# SCH.net
KiCad netlist of a schematic drawn in EasyEDA
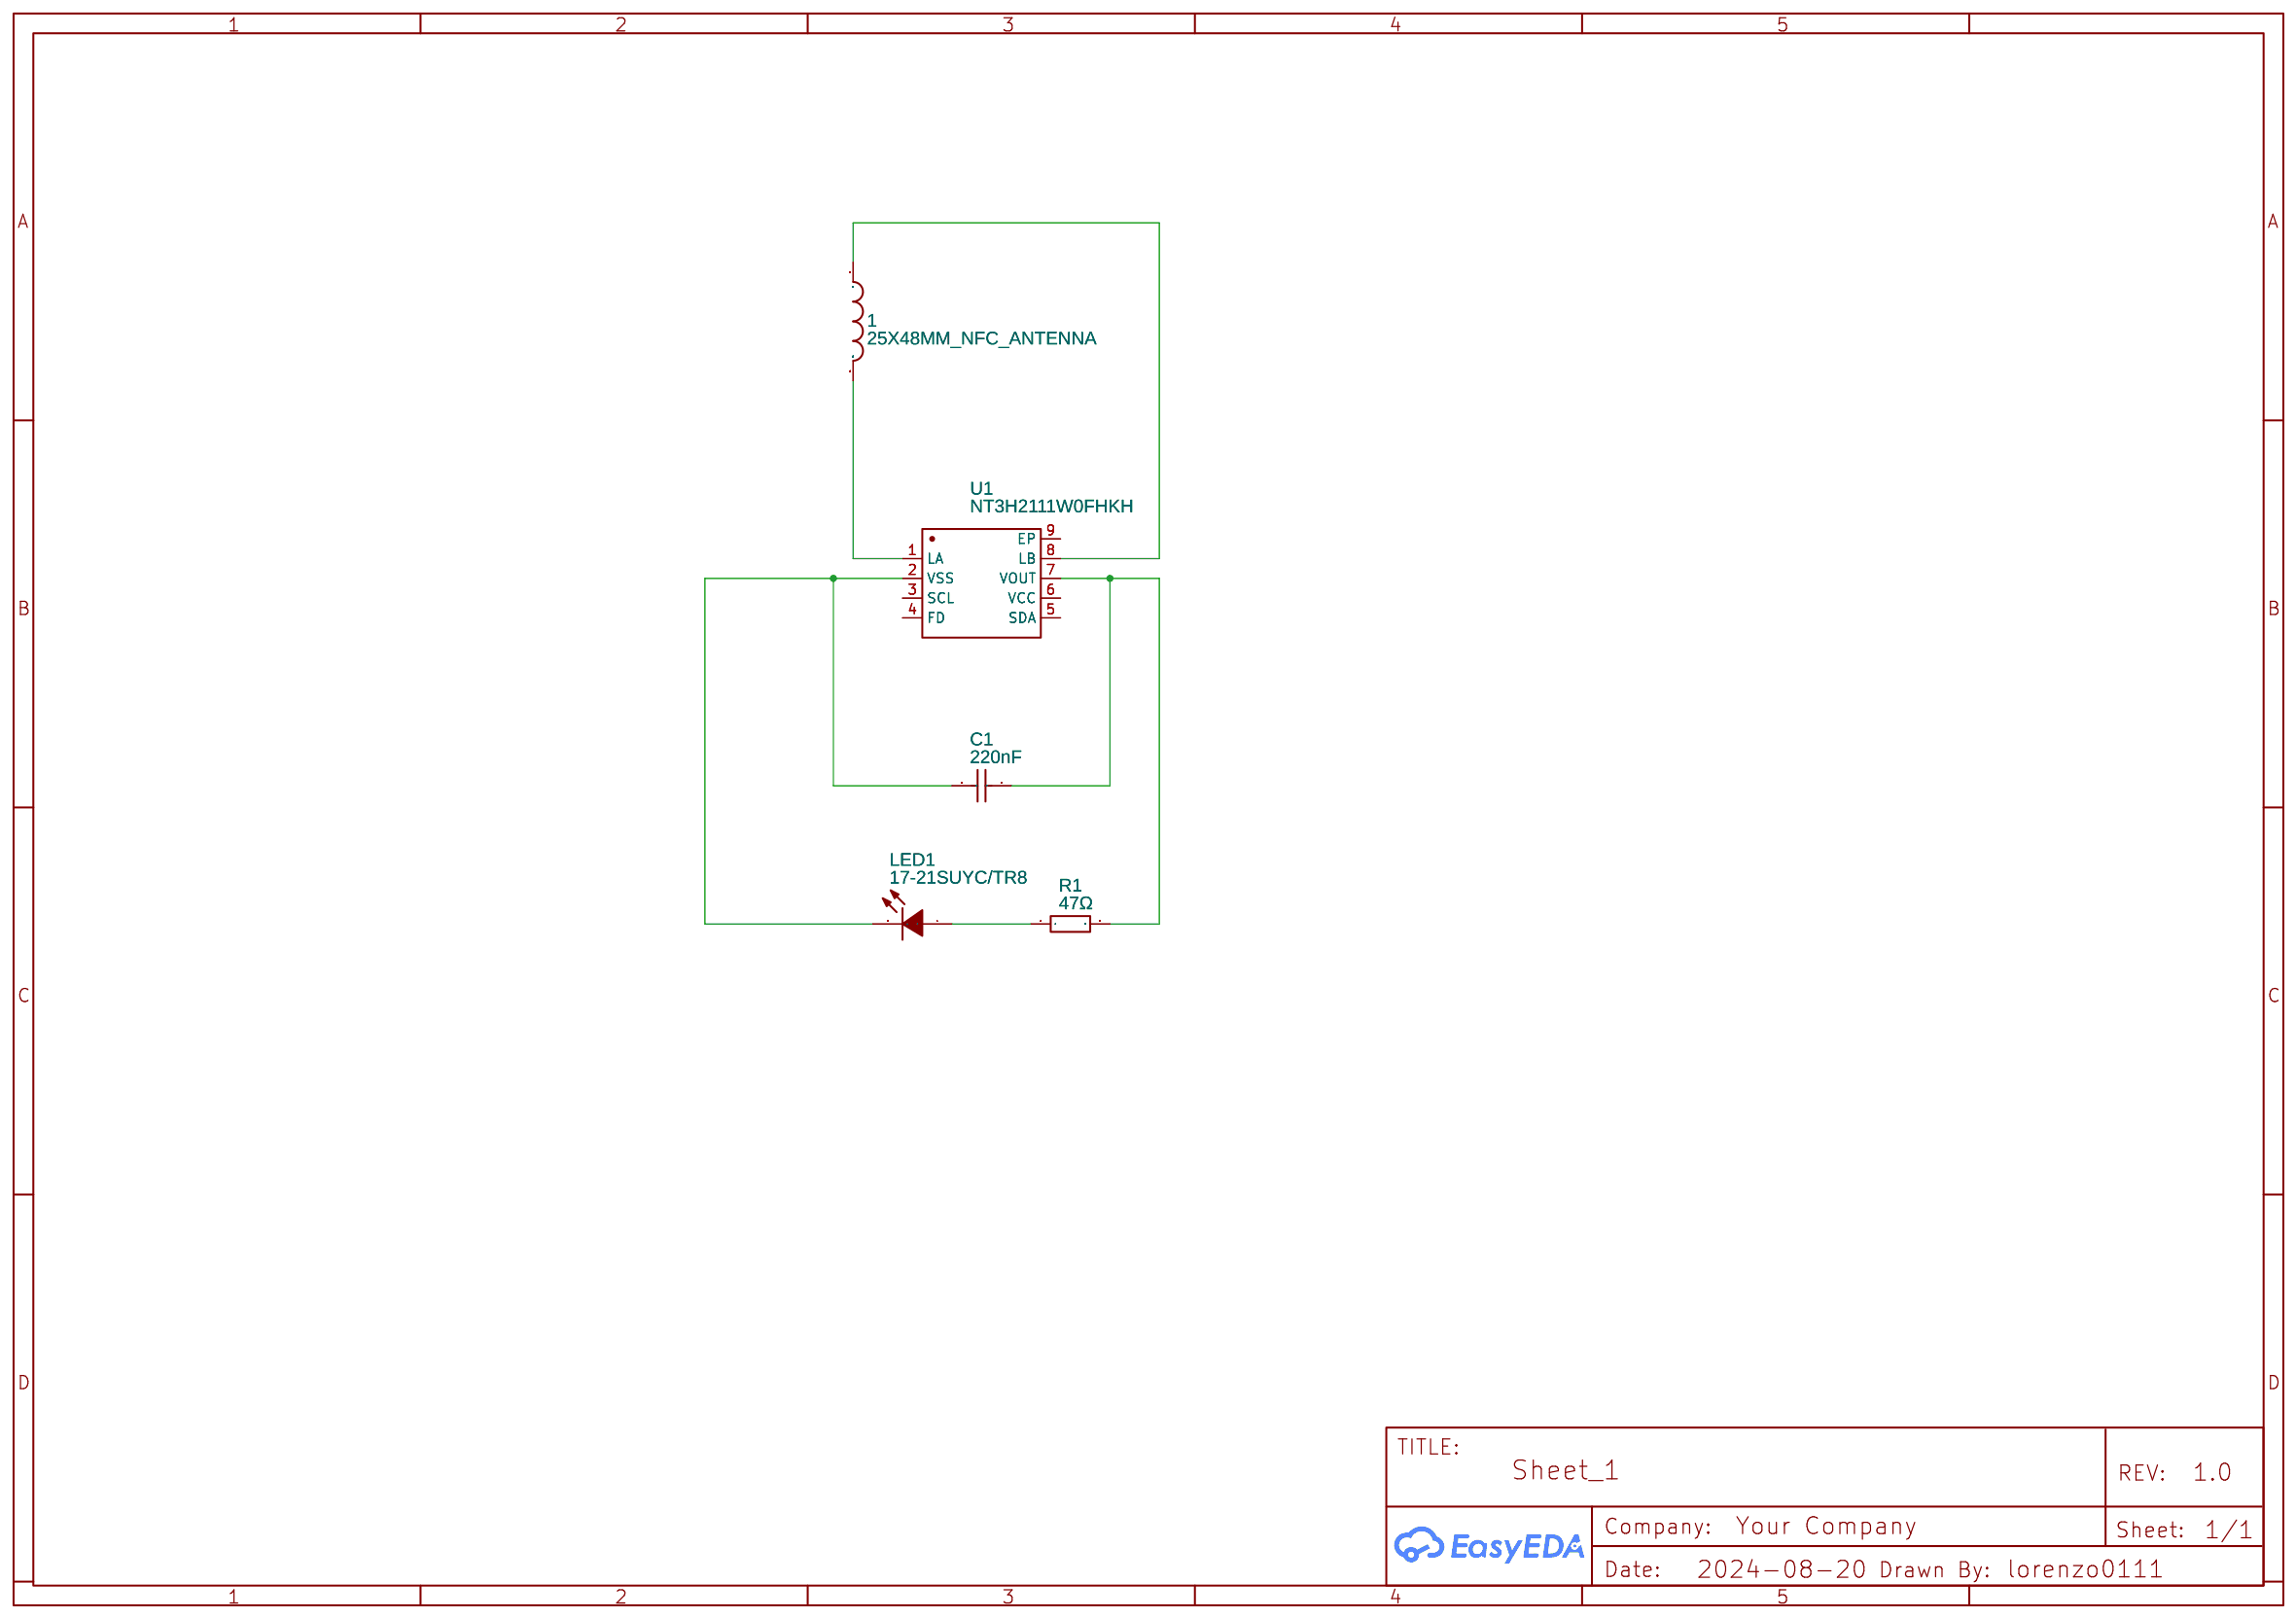
[diagram p0: schematic sheet]

(export (version "E")
  (design (tool "Eeschema 10.0.6"))
  (components
    (comp (ref "1") (value "25X48MM_NFC_ANTENNA") (libsource (lib "") (part "25X48MM_NFC_ANTENNA")))
    (comp (ref "C1")
      (value "220nF")
      (fields
        (field (name "Manufacturer Part") "CL10B224KA8NNNC")
        (field (name "Manufacturer") "SAMSUNG(三星)")
      )
      (libsource (lib "") (part "CL10B224KA8NNNC"))
    )
    (comp (ref "LED1")
      (value "17-21SUYC/TR8")
      (fields (field (name "Manufacturer Part") "KT-0805黄灯") (field (name "Manufacturer") "KENTO"))
      (libsource (lib "") (part "17-21SUYC/TR8"))
    )
    (comp (ref "R1")
      (value "47Ω")
      (fields
        (field (name "Manufacturer Part") "0603WAF470JT5E")
        (field (name "Manufacturer") "UNI-ROYAL(厚声)")
      )
      (libsource (lib "") (part "0603WAF470JT5E"))
    )
    (comp (ref "U1")
      (value "NT3H2111W0FHKH")
      (fields (field (name "Manufacturer") "NXP(恩智浦)"))
      (libsource (lib "") (part "NT3H2111W0FHKH"))
    )
  )
  (nets
    (net (code "1") (name "Net-(LED1-+)") (class "Default")
      (node (ref "LED1") (pin "1") (pinfunction "+_1") (pintype "unspecified"))
      (node (ref "R1") (pin "1") (pinfunction "1_1") (pintype "input"))
    )
    (net (code "2") (name "Net-(LED1--)") (class "Default")
      (node (ref "C1") (pin "1") (pinfunction "1_1") (pintype "input"))
      (node (ref "LED1") (pin "2") (pinfunction "-_2") (pintype "unspecified"))
      (node (ref "U1") (pin "2") (pinfunction "VSS_2") (pintype "unspecified"))
    )
    (net (code "3") (name "Net-(U1-LA)") (class "Default")
      (node (ref "1") (pin "P$2") (pinfunction "P$2_P$2") (pintype "bidirectional"))
      (node (ref "U1") (pin "1") (pinfunction "LA_1") (pintype "unspecified"))
    )
    (net (code "4") (name "Net-(U1-LB)") (class "Default")
      (node (ref "1") (pin "P$1") (pinfunction "P$1_P$1") (pintype "bidirectional"))
      (node (ref "U1") (pin "8") (pinfunction "LB_8") (pintype "unspecified"))
    )
    (net (code "5") (name "Net-(U1-VOUT)") (class "Default")
      (node (ref "C1") (pin "2") (pinfunction "2_2") (pintype "input"))
      (node (ref "R1") (pin "2") (pinfunction "2_2") (pintype "input"))
      (node (ref "U1") (pin "7") (pinfunction "VOUT_7") (pintype "unspecified"))
    )
    (net (code "6") (name "unconnected-(U1-EP-Pad9)") (class "Default")
      (node (ref "U1") (pin "9") (pinfunction "EP_9") (pintype "unspecified"))
    )
    (net (code "7") (name "unconnected-(U1-FD-Pad4)") (class "Default")
      (node (ref "U1") (pin "4") (pinfunction "FD_4") (pintype "unspecified"))
    )
    (net (code "8") (name "unconnected-(U1-SCL-Pad3)") (class "Default")
      (node (ref "U1") (pin "3") (pinfunction "SCL_3") (pintype "unspecified"))
    )
    (net (code "9") (name "unconnected-(U1-SDA-Pad5)") (class "Default")
      (node (ref "U1") (pin "5") (pinfunction "SDA_5") (pintype "unspecified"))
    )
    (net (code "10") (name "unconnected-(U1-VCC-Pad6)") (class "Default")
      (node (ref "U1") (pin "6") (pinfunction "VCC_6") (pintype "unspecified"))
    )
  )
)
